# Trix-Loco-PCB.net
KiCad netlist of a schematic drawn in EasyEDA
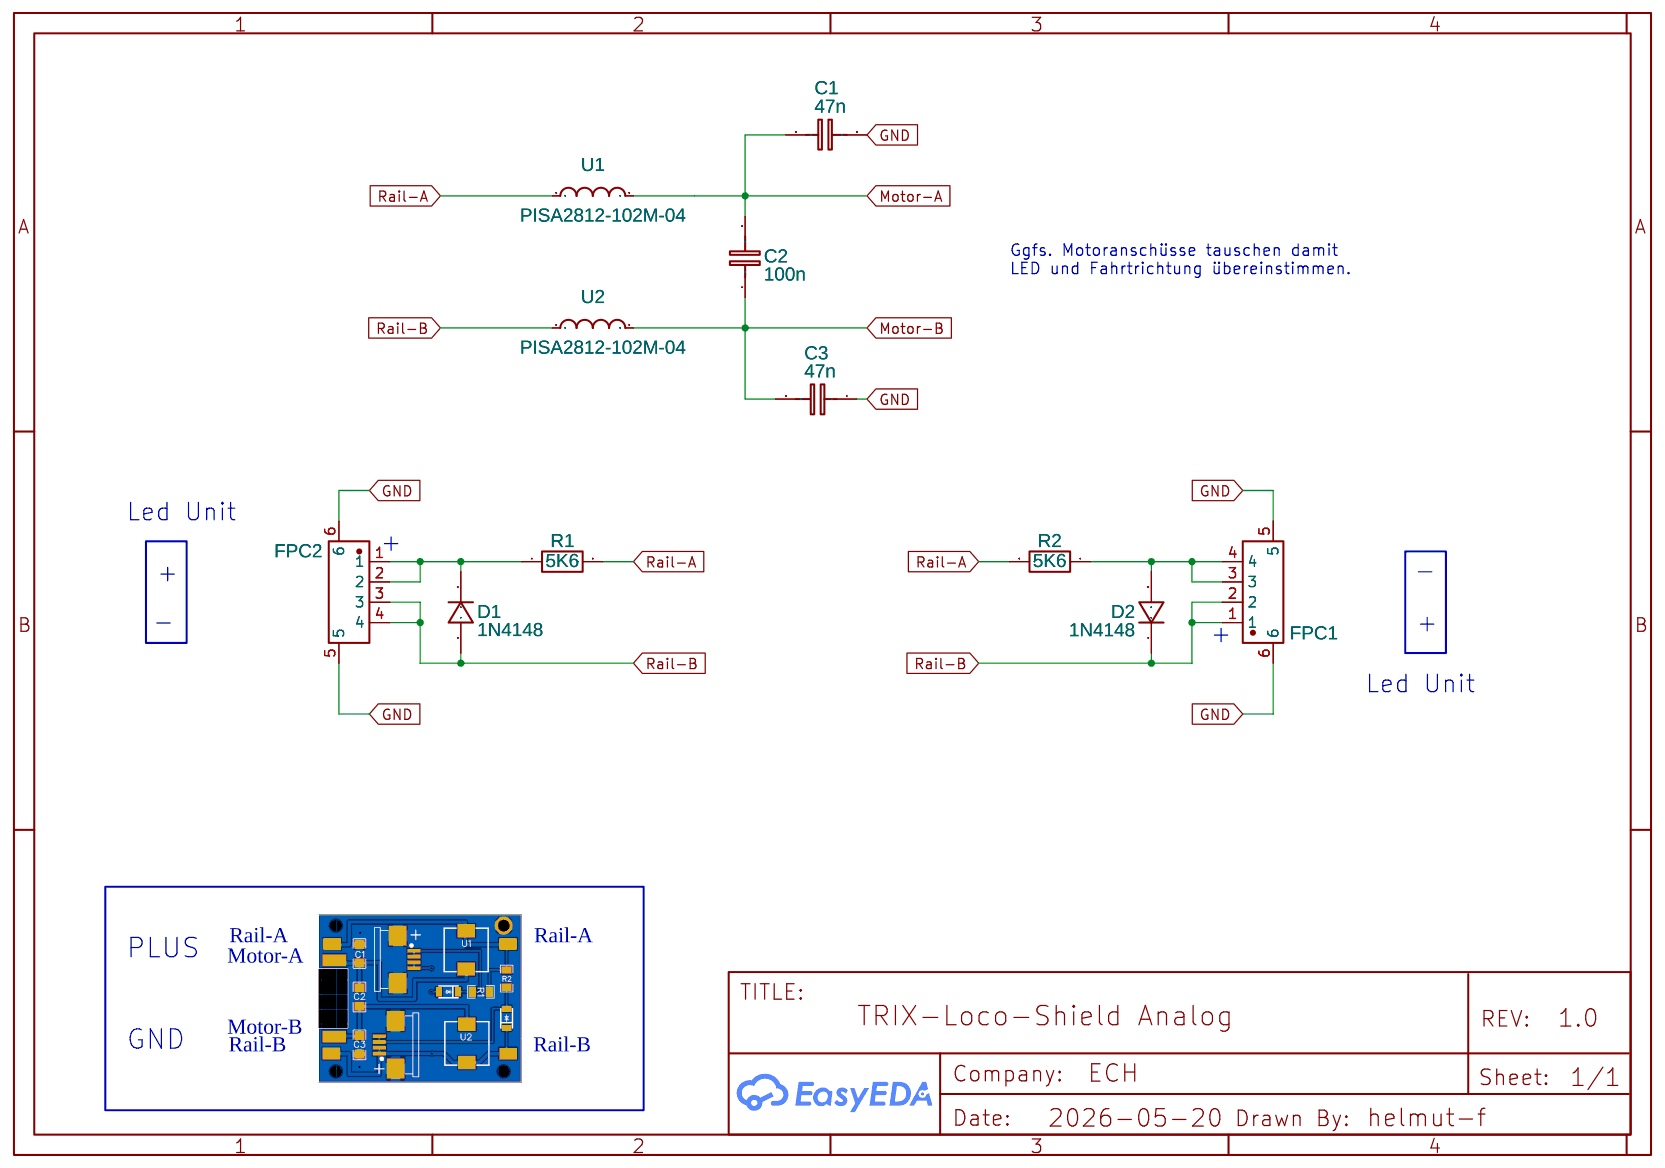
[diagram p0: schematic sheet]

(export (version "E")
  (design (tool "Eeschema 10.0.6"))
  (components
    (comp (ref "C1") (value "47n") (libsource (lib "") (part "C_1206_EU_2")))
    (comp (ref "C2") (value "100n") (libsource (lib "") (part "C_1206_EU")))
    (comp (ref "C3") (value "47n") (libsource (lib "") (part "C_1206_EU_1")))
    (comp (ref "D1")
      (value "1N4148")
      (fields (field (name "Manufacturer") "SEMTECH"))
      (libsource (lib "") (part "1N4148_1"))
    )
    (comp (ref "D2")
      (value "1N4148")
      (fields (field (name "Manufacturer") "SEMTECH"))
      (libsource (lib "") (part "1N4148"))
    )
    (comp (ref "FPC1") (value "FPC-4PIN-1.0MM-上接") (libsource (lib "") (part "FPC-4PIN-1.0MM-上接")))
    (comp (ref "FPC2") (value "FPC-4PIN-1.0MM-上接") (libsource (lib "") (part "FPC-4PIN-1.0MM-上接_1")))
    (comp (ref "R1") (value "5K6") (libsource (lib "") (part "R_1206_EU")))
    (comp (ref "R2") (value "5K6") (libsource (lib "") (part "R_1206_EU_1")))
    (comp (ref "U1") (value "PISA2812-102M-04") (libsource (lib "") (part "PISA2812-102M-04")))
    (comp (ref "U2") (value "PISA2812-102M-04") (libsource (lib "") (part "PISA2812-102M-04")))
  )
  (nets
    (net (code "1") (name "GND") (class "Default")
      (node (ref "C1") (pin "2") (pinfunction "2_2") (pintype "unspecified"))
      (node (ref "C3") (pin "1") (pinfunction "1_1") (pintype "unspecified"))
      (node (ref "FPC1") (pin "5") (pinfunction "5_5") (pintype "unspecified"))
      (node (ref "FPC1") (pin "6") (pinfunction "6_6") (pintype "unspecified"))
      (node (ref "FPC2") (pin "5") (pinfunction "5_5") (pintype "unspecified"))
      (node (ref "FPC2") (pin "6") (pinfunction "6_6") (pintype "unspecified"))
    )
    (net (code "2") (name "Motor-A") (class "Default")
      (node (ref "C1") (pin "1") (pinfunction "1_1") (pintype "unspecified"))
      (node (ref "C2") (pin "2") (pinfunction "2_2") (pintype "unspecified"))
      (node (ref "U1") (pin "2") (pinfunction "2_2") (pintype "unspecified"))
    )
    (net (code "3") (name "Motor-B") (class "Default")
      (node (ref "C2") (pin "1") (pinfunction "1_1") (pintype "unspecified"))
      (node (ref "C3") (pin "2") (pinfunction "2_2") (pintype "unspecified"))
      (node (ref "U2") (pin "2") (pinfunction "2_2") (pintype "unspecified"))
    )
    (net (code "4") (name "Net-(D1-2)") (class "Default")
      (node (ref "D1") (pin "1") (pinfunction "2_1") (pintype "unspecified"))
      (node (ref "FPC2") (pin "1") (pinfunction "1_1") (pintype "unspecified"))
      (node (ref "FPC2") (pin "2") (pinfunction "2_2") (pintype "unspecified"))
      (node (ref "R1") (pin "1") (pinfunction "1_1") (pintype "unspecified"))
    )
    (net (code "5") (name "Net-(D2-1)") (class "Default")
      (node (ref "D2") (pin "2") (pinfunction "1_2") (pintype "unspecified"))
      (node (ref "FPC1") (pin "3") (pinfunction "3_3") (pintype "unspecified"))
      (node (ref "FPC1") (pin "4") (pinfunction "4_4") (pintype "unspecified"))
      (node (ref "R2") (pin "1") (pinfunction "1_1") (pintype "unspecified"))
    )
    (net (code "6") (name "Rail-A") (class "Default")
      (node (ref "R1") (pin "2") (pinfunction "2_2") (pintype "unspecified"))
      (node (ref "R2") (pin "2") (pinfunction "2_2") (pintype "unspecified"))
      (node (ref "U1") (pin "1") (pinfunction "1_1") (pintype "unspecified"))
    )
    (net (code "7") (name "Rail-B") (class "Default")
      (node (ref "D1") (pin "2") (pinfunction "1_2") (pintype "unspecified"))
      (node (ref "D2") (pin "1") (pinfunction "2_1") (pintype "unspecified"))
      (node (ref "FPC1") (pin "1") (pinfunction "1_1") (pintype "unspecified"))
      (node (ref "FPC1") (pin "2") (pinfunction "2_2") (pintype "unspecified"))
      (node (ref "FPC2") (pin "3") (pinfunction "3_3") (pintype "unspecified"))
      (node (ref "FPC2") (pin "4") (pinfunction "4_4") (pintype "unspecified"))
      (node (ref "U2") (pin "1") (pinfunction "1_1") (pintype "unspecified"))
    )
  )
)
